# radio_schematic.net
KiCad netlist of a schematic drawn in EAGLE
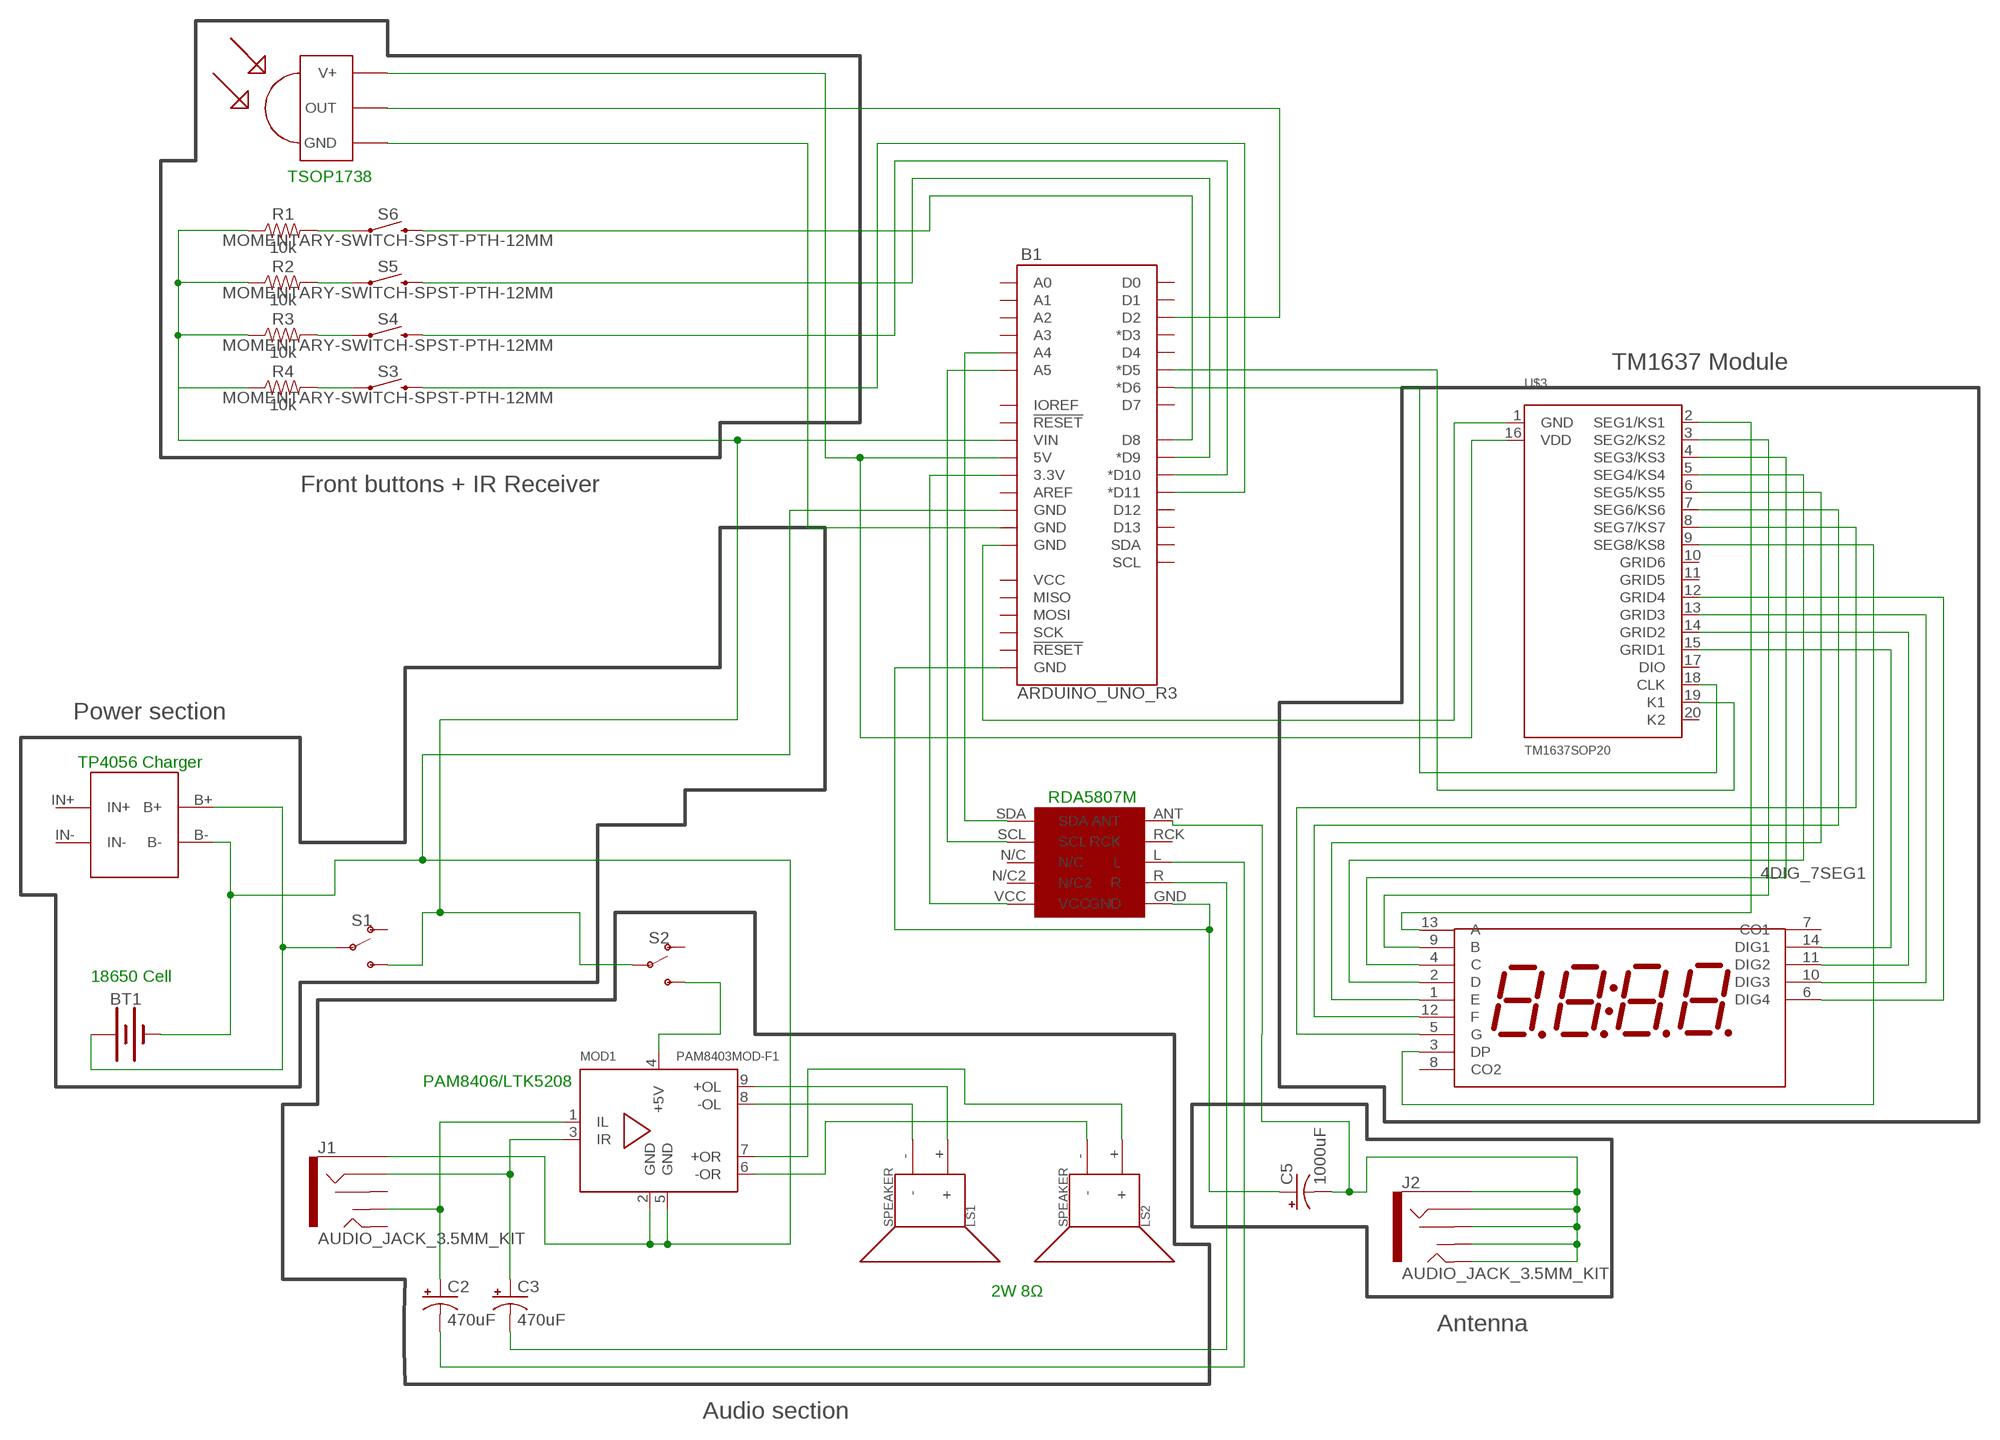
[diagram p0: schematic, sheet 1]

(export (version "E")
  (design (tool "Eeschema 10.0.6"))
  (components
    (comp (ref "4DIG_7SEG1")
      (value "4DIG_7SEG")
      (footprint "eagle-import:4DIG_7SEG")
      (libsource (lib "eagle-import") (part "4DIG_7SEG"))
    )
    (comp (ref "B1")
      (value "ARDUINO_UNO_R3")
      (footprint "eagle-import:ARDUINO_R3")
      (libsource (lib "eagle-import") (part "ARDUINO_UNO_R3"))
    )
    (comp (ref "BT1")
      (value "BATTERY-18650")
      (footprint "eagle-import:BATTERY_18650-HOLDER")
      (libsource (lib "eagle-import") (part "BATTERY-18650"))
    )
    (comp (ref "C2")
      (value "470uF")
      (footprint "eagle-import:CPOL-RADIAL-2.5MM-6.5MM")
      (libsource (lib "eagle-import") (part "100UF-POLAR-RADIAL-2.5MM-25V-20%"))
    )
    (comp (ref "C3")
      (value "470uF")
      (footprint "eagle-import:CPOL-RADIAL-2.5MM-6.5MM")
      (libsource (lib "eagle-import") (part "100UF-POLAR-RADIAL-2.5MM-25V-20%"))
    )
    (comp (ref "C5")
      (value "1000uF")
      (footprint "eagle-import:CPOL-RADIAL-2.5MM-6.5MM")
      (libsource (lib "eagle-import") (part "100UF-POLAR-RADIAL-2.5MM-25V-20%"))
    )
    (comp (ref "J1")
      (value "AUDIO_JACK_3.5MM_KIT")
      (footprint "eagle-import:AUDIO-JACK-KIT")
      (libsource (lib "eagle-import") (part "AUDIO_JACK_3.5MM_KIT"))
    )
    (comp (ref "J2")
      (value "AUDIO_JACK_3.5MM_KIT")
      (footprint "eagle-import:AUDIO-JACK-KIT")
      (libsource (lib "eagle-import") (part "AUDIO_JACK_3.5MM_KIT"))
    )
    (comp (ref "LS1")
      (value "SPEAKER")
      (footprint "eagle-import:PCB_MOUNT_SPEAKER")
      (libsource (lib "eagle-import") (part "SPEAKER"))
    )
    (comp (ref "LS2")
      (value "SPEAKER")
      (footprint "eagle-import:PCB_MOUNT_SPEAKER")
      (libsource (lib "eagle-import") (part "SPEAKER"))
    )
    (comp (ref "MOD1")
      (value "PAM8403MOD-F1")
      (footprint "eagle-import:PAM8403MOD1")
      (libsource (lib "eagle-import") (part "PAM8403MOD-F1"))
    )
    (comp (ref "R1")
      (value "10k")
      (footprint "eagle-import:AXIAL-0.3")
      (libsource (lib "eagle-import") (part "10KOHM-HORIZ-1/4W-5%"))
    )
    (comp (ref "R2")
      (value "10k")
      (footprint "eagle-import:AXIAL-0.3")
      (libsource (lib "eagle-import") (part "10KOHM-HORIZ-1/4W-5%"))
    )
    (comp (ref "R3")
      (value "10k")
      (footprint "eagle-import:AXIAL-0.3")
      (libsource (lib "eagle-import") (part "10KOHM-HORIZ-1/4W-5%"))
    )
    (comp (ref "R4")
      (value "10k")
      (footprint "eagle-import:AXIAL-0.3")
      (libsource (lib "eagle-import") (part "10KOHM-HORIZ-1/4W-5%"))
    )
    (comp (ref "S1")
      (value "SWITCH-SPDT-PTH-11.6X4.0MM-SHORT_LEADS")
      (footprint "eagle-import:SWITCH_SPDT_PTH_11.6X4.0MM")
      (libsource (lib "eagle-import") (part "SWITCH-SPDT-PTH-11.6X4.0MM-SHORT_LEADS"))
    )
    (comp (ref "S2")
      (value "SWITCH-SPDT-PTH-11.6X4.0MM-SHORT_LEADS")
      (footprint "eagle-import:SWITCH_SPDT_PTH_11.6X4.0MM")
      (libsource (lib "eagle-import") (part "SWITCH-SPDT-PTH-11.6X4.0MM-SHORT_LEADS"))
    )
    (comp (ref "S3")
      (value "MOMENTARY-SWITCH-SPST-PTH-12MM")
      (footprint "eagle-import:TACTILE_SWITCH_PTH_12MM")
      (libsource (lib "eagle-import") (part "MOMENTARY-SWITCH-SPST-PTH-12MM"))
    )
    (comp (ref "S4")
      (value "MOMENTARY-SWITCH-SPST-PTH-12MM")
      (footprint "eagle-import:TACTILE_SWITCH_PTH_12MM")
      (libsource (lib "eagle-import") (part "MOMENTARY-SWITCH-SPST-PTH-12MM"))
    )
    (comp (ref "S5")
      (value "MOMENTARY-SWITCH-SPST-PTH-12MM")
      (footprint "eagle-import:TACTILE_SWITCH_PTH_12MM")
      (libsource (lib "eagle-import") (part "MOMENTARY-SWITCH-SPST-PTH-12MM"))
    )
    (comp (ref "S6")
      (value "MOMENTARY-SWITCH-SPST-PTH-12MM")
      (footprint "eagle-import:TACTILE_SWITCH_PTH_12MM")
      (libsource (lib "eagle-import") (part "MOMENTARY-SWITCH-SPST-PTH-12MM"))
    )
    (comp (ref "U$1")
      (value "RDA")
      (footprint "eagle-import:RDA")
      (libsource (lib "eagle-import") (part "RDA"))
    )
    (comp (ref "U$2")
      (value "TSOP1738")
      (footprint "eagle-import:TSOP17XX")
      (libsource (lib "eagle-import") (part "TSOP1738"))
    )
    (comp (ref "U$3")
      (value "TM1637SOP20")
      (footprint "eagle-import:SOP20")
      (libsource (lib "eagle-import") (part "TM1637SOP20"))
    )
    (comp (ref "U$4")
      (value "TP4056")
      (footprint "eagle-import:TP4056")
      (libsource (lib "eagle-import") (part "TP4056"))
    )
  )
  (nets
    (net (code "1") (name "Net-(4DIG_7SEG1-A)") (class "Default")
      (node (ref "4DIG_7SEG1") (pin "13") (pinfunction "A_13") (pintype "bidirectional"))
      (node (ref "U$3") (pin "2") (pinfunction "SEG1/KS1_2") (pintype "bidirectional"))
    )
    (net (code "2") (name "Net-(4DIG_7SEG1-B)") (class "Default")
      (node (ref "4DIG_7SEG1") (pin "9") (pinfunction "B_9") (pintype "bidirectional"))
      (node (ref "U$3") (pin "3") (pinfunction "SEG2/KS2_3") (pintype "bidirectional"))
    )
    (net (code "3") (name "Net-(4DIG_7SEG1-C)") (class "Default")
      (node (ref "4DIG_7SEG1") (pin "4") (pinfunction "C_4") (pintype "bidirectional"))
      (node (ref "U$3") (pin "4") (pinfunction "SEG3/KS3_4") (pintype "bidirectional"))
    )
    (net (code "4") (name "Net-(4DIG_7SEG1-D)") (class "Default")
      (node (ref "4DIG_7SEG1") (pin "2") (pinfunction "D_2") (pintype "bidirectional"))
      (node (ref "U$3") (pin "5") (pinfunction "SEG4/KS4_5") (pintype "bidirectional"))
    )
    (net (code "5") (name "Net-(4DIG_7SEG1-DIG1)") (class "Default")
      (node (ref "4DIG_7SEG1") (pin "14") (pinfunction "DIG1_14") (pintype "bidirectional"))
      (node (ref "U$3") (pin "15") (pinfunction "GRID1_15") (pintype "bidirectional"))
    )
    (net (code "6") (name "Net-(4DIG_7SEG1-DIG2)") (class "Default")
      (node (ref "4DIG_7SEG1") (pin "11") (pinfunction "DIG2_11") (pintype "bidirectional"))
      (node (ref "U$3") (pin "14") (pinfunction "GRID2_14") (pintype "bidirectional"))
    )
    (net (code "7") (name "Net-(4DIG_7SEG1-DIG3)") (class "Default")
      (node (ref "4DIG_7SEG1") (pin "10") (pinfunction "DIG3_10") (pintype "bidirectional"))
      (node (ref "U$3") (pin "13") (pinfunction "GRID3_13") (pintype "bidirectional"))
    )
    (net (code "8") (name "Net-(4DIG_7SEG1-DIG4)") (class "Default")
      (node (ref "4DIG_7SEG1") (pin "6") (pinfunction "DIG4_6") (pintype "bidirectional"))
      (node (ref "U$3") (pin "12") (pinfunction "GRID4_12") (pintype "bidirectional"))
    )
    (net (code "9") (name "Net-(4DIG_7SEG1-DP)") (class "Default")
      (node (ref "4DIG_7SEG1") (pin "3") (pinfunction "DP_3") (pintype "bidirectional"))
      (node (ref "U$3") (pin "9") (pinfunction "SEG8/KS8_9") (pintype "bidirectional"))
    )
    (net (code "10") (name "Net-(4DIG_7SEG1-E)") (class "Default")
      (node (ref "4DIG_7SEG1") (pin "1") (pinfunction "E_1") (pintype "bidirectional"))
      (node (ref "U$3") (pin "6") (pinfunction "SEG5/KS5_6") (pintype "bidirectional"))
    )
    (net (code "11") (name "Net-(4DIG_7SEG1-F)") (class "Default")
      (node (ref "4DIG_7SEG1") (pin "12") (pinfunction "F_12") (pintype "bidirectional"))
      (node (ref "U$3") (pin "7") (pinfunction "SEG6/KS6_7") (pintype "bidirectional"))
    )
    (net (code "12") (name "Net-(4DIG_7SEG1-G)") (class "Default")
      (node (ref "4DIG_7SEG1") (pin "5") (pinfunction "G_5") (pintype "bidirectional"))
      (node (ref "U$3") (pin "8") (pinfunction "SEG7/KS7_8") (pintype "bidirectional"))
    )
    (net (code "13") (name "Net-(B1-*D5)") (class "Default")
      (node (ref "B1") (pin "D5") (pinfunction "*D5_D5") (pintype "bidirectional"))
      (node (ref "U$3") (pin "19") (pinfunction "K1_19") (pintype "bidirectional"))
    )
    (net (code "14") (name "Net-(B1-*D6)") (class "Default")
      (node (ref "B1") (pin "D6") (pinfunction "*D6_D6") (pintype "bidirectional"))
      (node (ref "U$3") (pin "18") (pinfunction "CLK_18") (pintype "bidirectional"))
    )
    (net (code "15") (name "Net-(B1-*D9)") (class "Default")
      (node (ref "B1") (pin "D9") (pinfunction "*D9_D9") (pintype "bidirectional"))
      (node (ref "S5") (pin "3") (pinfunction "2_3") (pintype "passive"))
    )
    (net (code "16") (name "Net-(B1-*D10)") (class "Default")
      (node (ref "B1") (pin "D10") (pinfunction "*D10_D10") (pintype "bidirectional"))
      (node (ref "S4") (pin "3") (pinfunction "2_3") (pintype "passive"))
    )
    (net (code "17") (name "Net-(B1-*D11)") (class "Default")
      (node (ref "B1") (pin "D11") (pinfunction "*D11_D11") (pintype "bidirectional"))
      (node (ref "S3") (pin "3") (pinfunction "2_3") (pintype "passive"))
    )
    (net (code "18") (name "Net-(B1-GND-PadGND@3)") (class "Default")
      (node (ref "B1") (pin "GND@3") (pinfunction "GND_GND@3") (pintype "bidirectional"))
      (node (ref "U$2") (pin "GND") (pinfunction "GND_GND") (pintype "bidirectional"))
    )
    (net (code "19") (name "Net-(B1-Pad3.3V)") (class "Default")
      (node (ref "B1") (pin "3.3V") (pinfunction "3.3V_3.3V") (pintype "bidirectional"))
      (node (ref "U$1") (pin "VCC") (pinfunction "VCC_VCC") (pintype "power_in"))
    )
    (net (code "20") (name "Net-(B1-PadA4)") (class "Default")
      (node (ref "B1") (pin "A4") (pinfunction "A4_A4") (pintype "bidirectional"))
      (node (ref "U$1") (pin "SDA") (pinfunction "SDA_SDA") (pintype "bidirectional"))
    )
    (net (code "21") (name "Net-(B1-PadA5)") (class "Default")
      (node (ref "B1") (pin "A5") (pinfunction "A5_A5") (pintype "bidirectional"))
      (node (ref "U$1") (pin "SCL") (pinfunction "SCL_SCL") (pintype "bidirectional"))
    )
    (net (code "22") (name "Net-(B1-PadD2)") (class "Default")
      (node (ref "B1") (pin "D2") (pinfunction "D2_D2") (pintype "bidirectional"))
      (node (ref "U$2") (pin "OUT") (pinfunction "OUT_OUT") (pintype "bidirectional"))
    )
    (net (code "23") (name "Net-(BT1-+)") (class "Default")
      (node (ref "BT1") (pin "PWR@1") (pinfunction "+_PWR@1") (pintype "power_in"))
      (node (ref "S1") (pin "2") (pinfunction "P_2") (pintype "passive"))
      (node (ref "U$4") (pin "B+") (pinfunction "B+_B+") (pintype "bidirectional"))
    )
    (net (code "24") (name "Net-(BT1--)") (class "Default")
      (node (ref "B1") (pin "GND@4") (pinfunction "GND_GND@4") (pintype "bidirectional"))
      (node (ref "BT1") (pin "GND@1") (pinfunction "-_GND@1") (pintype "power_in"))
      (node (ref "J1") (pin "SLEEVE") (pinfunction "SLEEVE_SLEEVE") (pintype "bidirectional"))
      (node (ref "MOD1") (pin "2") (pinfunction "GND_2") (pintype "power_in"))
      (node (ref "MOD1") (pin "5") (pinfunction "GND_5") (pintype "power_in"))
      (node (ref "U$4") (pin "B-") (pinfunction "B-_B-") (pintype "bidirectional"))
    )
    (net (code "25") (name "Net-(C2-+)") (class "Default")
      (node (ref "C2") (pin "1") (pinfunction "+_1") (pintype "passive"))
      (node (ref "J1") (pin "TSH") (pinfunction "TSH_TSH") (pintype "bidirectional"))
      (node (ref "MOD1") (pin "1") (pinfunction "IL_1") (pintype "passive"))
    )
    (net (code "26") (name "Net-(C2--)") (class "Default")
      (node (ref "C2") (pin "2") (pinfunction "-_2") (pintype "passive"))
      (node (ref "U$1") (pin "L") (pinfunction "L_L") (pintype "output"))
    )
    (net (code "27") (name "Net-(C3-+)") (class "Default")
      (node (ref "C3") (pin "1") (pinfunction "+_1") (pintype "passive"))
      (node (ref "J1") (pin "RING") (pinfunction "RING_RING") (pintype "bidirectional"))
      (node (ref "MOD1") (pin "3") (pinfunction "IR_3") (pintype "passive"))
    )
    (net (code "28") (name "Net-(C3--)") (class "Default")
      (node (ref "C3") (pin "2") (pinfunction "-_2") (pintype "passive"))
      (node (ref "U$1") (pin "R") (pinfunction "R_R") (pintype "output"))
    )
    (net (code "29") (name "Net-(C5-+)") (class "Default")
      (node (ref "B1") (pin "GND@1") (pinfunction "GND_GND@1") (pintype "bidirectional"))
      (node (ref "C5") (pin "1") (pinfunction "+_1") (pintype "passive"))
      (node (ref "U$1") (pin "GND") (pinfunction "GND_GND") (pintype "power_in"))
    )
    (net (code "30") (name "Net-(C5--)") (class "Default")
      (node (ref "C5") (pin "2") (pinfunction "-_2") (pintype "passive"))
      (node (ref "J2") (pin "RING") (pinfunction "RING_RING") (pintype "bidirectional"))
      (node (ref "J2") (pin "RSH") (pinfunction "RSH_RSH") (pintype "bidirectional"))
      (node (ref "J2") (pin "SLEEVE") (pinfunction "SLEEVE_SLEEVE") (pintype "bidirectional"))
      (node (ref "J2") (pin "TIP") (pinfunction "TIP_TIP") (pintype "bidirectional"))
      (node (ref "J2") (pin "TSH") (pinfunction "TSH_TSH") (pintype "bidirectional"))
      (node (ref "U$1") (pin "ANT") (pinfunction "ANT_ANT") (pintype "input"))
    )
    (net (code "31") (name "Net-(MOD1-+5V)") (class "Default")
      (node (ref "MOD1") (pin "4") (pinfunction "+5V_4") (pintype "power_in"))
      (node (ref "S2") (pin "3") (pinfunction "S_3") (pintype "passive"))
    )
    (net (code "32") (name "Net-(MOD1-+OL)") (class "Default")
      (node (ref "LS1") (pin "+") (pinfunction "+_+") (pintype "bidirectional"))
      (node (ref "MOD1") (pin "9") (pinfunction "+OL_9") (pintype "passive"))
    )
    (net (code "33") (name "Net-(MOD1-+OR)") (class "Default")
      (node (ref "LS2") (pin "+") (pinfunction "+_+") (pintype "bidirectional"))
      (node (ref "MOD1") (pin "7") (pinfunction "+OR_7") (pintype "passive"))
    )
    (net (code "34") (name "Net-(MOD1--OL)") (class "Default")
      (node (ref "LS1") (pin "-") (pinfunction "-_-") (pintype "bidirectional"))
      (node (ref "MOD1") (pin "8") (pinfunction "-OL_8") (pintype "passive"))
    )
    (net (code "35") (name "Net-(MOD1--OR)") (class "Default")
      (node (ref "LS2") (pin "-") (pinfunction "-_-") (pintype "bidirectional"))
      (node (ref "MOD1") (pin "6") (pinfunction "-OR_6") (pintype "passive"))
    )
    (net (code "36") (name "Net-(R1-1)") (class "Default")
      (node (ref "B1") (pin "VIN") (pinfunction "VIN_VIN") (pintype "bidirectional"))
      (node (ref "R1") (pin "P$1") (pinfunction "1_P$1") (pintype "passive"))
      (node (ref "R2") (pin "P$1") (pinfunction "1_P$1") (pintype "passive"))
      (node (ref "R3") (pin "P$1") (pinfunction "1_P$1") (pintype "passive"))
      (node (ref "R4") (pin "P$1") (pinfunction "1_P$1") (pintype "passive"))
      (node (ref "S1") (pin "3") (pinfunction "S_3") (pintype "passive"))
      (node (ref "S2") (pin "2") (pinfunction "P_2") (pintype "passive"))
    )
    (net (code "37") (name "Net-(R1-2)") (class "Default")
      (node (ref "R1") (pin "P$2") (pinfunction "2_P$2") (pintype "passive"))
      (node (ref "S6") (pin "1") (pinfunction "1_1") (pintype "passive"))
    )
    (net (code "38") (name "Net-(R2-2)") (class "Default")
      (node (ref "R2") (pin "P$2") (pinfunction "2_P$2") (pintype "passive"))
      (node (ref "S5") (pin "1") (pinfunction "1_1") (pintype "passive"))
    )
    (net (code "39") (name "Net-(R3-2)") (class "Default")
      (node (ref "R3") (pin "P$2") (pinfunction "2_P$2") (pintype "passive"))
      (node (ref "S4") (pin "1") (pinfunction "1_1") (pintype "passive"))
    )
    (net (code "40") (name "Net-(R4-2)") (class "Default")
      (node (ref "R4") (pin "P$2") (pinfunction "2_P$2") (pintype "passive"))
      (node (ref "S3") (pin "1") (pinfunction "1_1") (pintype "passive"))
    )
    (net (code "41") (name "Net-(S6-2)") (class "Default")
      (node (ref "B1") (pin "D8") (pinfunction "D8_D8") (pintype "bidirectional"))
      (node (ref "S6") (pin "3") (pinfunction "2_3") (pintype "passive"))
    )
    (net (code "42") (name "Net-(U$3-GND)") (class "Default")
      (node (ref "B1") (pin "GND@2") (pinfunction "GND_GND@2") (pintype "bidirectional"))
      (node (ref "U$3") (pin "1") (pinfunction "GND_1") (pintype "bidirectional"))
    )
    (net (code "43") (name "Net-(U$3-VDD)") (class "Default")
      (node (ref "B1") (pin "5V") (pinfunction "5V_5V") (pintype "bidirectional"))
      (node (ref "U$2") (pin "V+") (pinfunction "V+_V+") (pintype "bidirectional"))
      (node (ref "U$3") (pin "16") (pinfunction "VDD_16") (pintype "bidirectional"))
    )
    (net (code "44") (name "unconnected-(4DIG_7SEG1-CO1-Pad7)") (class "Default")
      (node (ref "4DIG_7SEG1") (pin "7") (pinfunction "CO1_7") (pintype "bidirectional"))
    )
    (net (code "45") (name "unconnected-(4DIG_7SEG1-CO2-Pad8)") (class "Default")
      (node (ref "4DIG_7SEG1") (pin "8") (pinfunction "CO2_8") (pintype "bidirectional"))
    )
    (net (code "46") (name "unconnected-(B1-*D3-PadD3)") (class "Default")
      (node (ref "B1") (pin "D3") (pinfunction "*D3_D3") (pintype "bidirectional"))
    )
    (net (code "47") (name "unconnected-(B1-PadA0)") (class "Default")
      (node (ref "B1") (pin "A0") (pinfunction "A0_A0") (pintype "bidirectional"))
    )
    (net (code "48") (name "unconnected-(B1-PadA1)") (class "Default")
      (node (ref "B1") (pin "A1") (pinfunction "A1_A1") (pintype "bidirectional"))
    )
    (net (code "49") (name "unconnected-(B1-PadA2)") (class "Default")
      (node (ref "B1") (pin "A2") (pinfunction "A2_A2") (pintype "bidirectional"))
    )
    (net (code "50") (name "unconnected-(B1-PadA3)") (class "Default")
      (node (ref "B1") (pin "A3") (pinfunction "A3_A3") (pintype "bidirectional"))
    )
    (net (code "51") (name "unconnected-(B1-PadAREF)") (class "Default")
      (node (ref "B1") (pin "AREF") (pinfunction "AREF_AREF") (pintype "bidirectional"))
    )
    (net (code "52") (name "unconnected-(B1-PadD0)") (class "Default")
      (node (ref "B1") (pin "D0") (pinfunction "D0_D0") (pintype "bidirectional"))
    )
    (net (code "53") (name "unconnected-(B1-PadD1)") (class "Default")
      (node (ref "B1") (pin "D1") (pinfunction "D1_D1") (pintype "bidirectional"))
    )
    (net (code "54") (name "unconnected-(B1-PadD4)") (class "Default")
      (node (ref "B1") (pin "D4") (pinfunction "D4_D4") (pintype "bidirectional"))
    )
    (net (code "55") (name "unconnected-(B1-PadD7)") (class "Default")
      (node (ref "B1") (pin "D7") (pinfunction "D7_D7") (pintype "bidirectional"))
    )
    (net (code "56") (name "unconnected-(B1-PadD12)") (class "Default")
      (node (ref "B1") (pin "D12") (pinfunction "D12_D12") (pintype "bidirectional"))
    )
    (net (code "57") (name "unconnected-(B1-PadD13)") (class "Default")
      (node (ref "B1") (pin "D13") (pinfunction "D13_D13") (pintype "bidirectional"))
    )
    (net (code "58") (name "unconnected-(B1-PadIOREF)") (class "Default")
      (node (ref "B1") (pin "IOREF") (pinfunction "IOREF_IOREF") (pintype "bidirectional"))
    )
    (net (code "59") (name "unconnected-(B1-PadMISO)") (class "Default")
      (node (ref "B1") (pin "MISO") (pinfunction "MISO_MISO") (pintype "bidirectional"))
    )
    (net (code "60") (name "unconnected-(B1-PadMOSI)") (class "Default")
      (node (ref "B1") (pin "MOSI") (pinfunction "MOSI_MOSI") (pintype "bidirectional"))
    )
    (net (code "61") (name "unconnected-(B1-PadSCK)") (class "Default")
      (node (ref "B1") (pin "SCK") (pinfunction "SCK_SCK") (pintype "bidirectional"))
    )
    (net (code "62") (name "unconnected-(B1-PadSCL)") (class "Default")
      (node (ref "B1") (pin "SCL") (pinfunction "SCL_SCL") (pintype "bidirectional"))
    )
    (net (code "63") (name "unconnected-(B1-PadSDA)") (class "Default")
      (node (ref "B1") (pin "SDA") (pinfunction "SDA_SDA") (pintype "bidirectional"))
    )
    (net (code "64") (name "unconnected-(B1-PadVCC)") (class "Default")
      (node (ref "B1") (pin "VCC") (pinfunction "VCC_VCC") (pintype "bidirectional"))
    )
    (net (code "65") (name "unconnected-(B1-~{RESET}-PadRESET@1)") (class "Default")
      (node (ref "B1") (pin "RESET@1") (pinfunction "~{RESET}_RESET@1") (pintype "bidirectional"))
    )
    (net (code "66") (name "unconnected-(B1-~{RESET}-PadRESET@2)") (class "Default")
      (node (ref "B1") (pin "RESET@2") (pinfunction "~{RESET}_RESET@2") (pintype "bidirectional"))
    )
    (net (code "67") (name "unconnected-(J1-PadRSH)") (class "Default")
      (node (ref "J1") (pin "RSH") (pinfunction "RSH_RSH") (pintype "bidirectional"))
    )
    (net (code "68") (name "unconnected-(J1-PadTIP)") (class "Default")
      (node (ref "J1") (pin "TIP") (pinfunction "TIP_TIP") (pintype "bidirectional"))
    )
    (net (code "69") (name "unconnected-(S1-O-Pad1)") (class "Default")
      (node (ref "S1") (pin "1") (pinfunction "O_1") (pintype "passive"))
    )
    (net (code "70") (name "unconnected-(S2-O-Pad1)") (class "Default")
      (node (ref "S2") (pin "1") (pinfunction "O_1") (pintype "passive"))
    )
    (net (code "71") (name "unconnected-(U$1-PadN{slash}C)") (class "Default")
      (node (ref "U$1") (pin "N/C") (pinfunction "N/C_N/C") (pintype "passive"))
    )
    (net (code "72") (name "unconnected-(U$1-PadN{slash}C2)") (class "Default")
      (node (ref "U$1") (pin "N/C2") (pinfunction "N/C2_N/C2") (pintype "passive"))
    )
    (net (code "73") (name "unconnected-(U$1-PadRCK)") (class "Default")
      (node (ref "U$1") (pin "RCK") (pinfunction "RCK_RCK") (pintype "bidirectional"))
    )
    (net (code "74") (name "unconnected-(U$3-DIO-Pad17)") (class "Default")
      (node (ref "U$3") (pin "17") (pinfunction "DIO_17") (pintype "bidirectional"))
    )
    (net (code "75") (name "unconnected-(U$3-GRID5-Pad11)") (class "Default")
      (node (ref "U$3") (pin "11") (pinfunction "GRID5_11") (pintype "bidirectional"))
    )
    (net (code "76") (name "unconnected-(U$3-GRID6-Pad10)") (class "Default")
      (node (ref "U$3") (pin "10") (pinfunction "GRID6_10") (pintype "bidirectional"))
    )
    (net (code "77") (name "unconnected-(U$3-K2-Pad20)") (class "Default")
      (node (ref "U$3") (pin "20") (pinfunction "K2_20") (pintype "bidirectional"))
    )
    (net (code "78") (name "unconnected-(U$4-PadIN+)") (class "Default")
      (node (ref "U$4") (pin "IN+") (pinfunction "IN+_IN+") (pintype "bidirectional"))
    )
    (net (code "79") (name "unconnected-(U$4-PadIN-)") (class "Default")
      (node (ref "U$4") (pin "IN-") (pinfunction "IN-_IN-") (pintype "bidirectional"))
    )
  )
)
